# design.net
KiCad netlist of a schematic drawn in Altium Designer
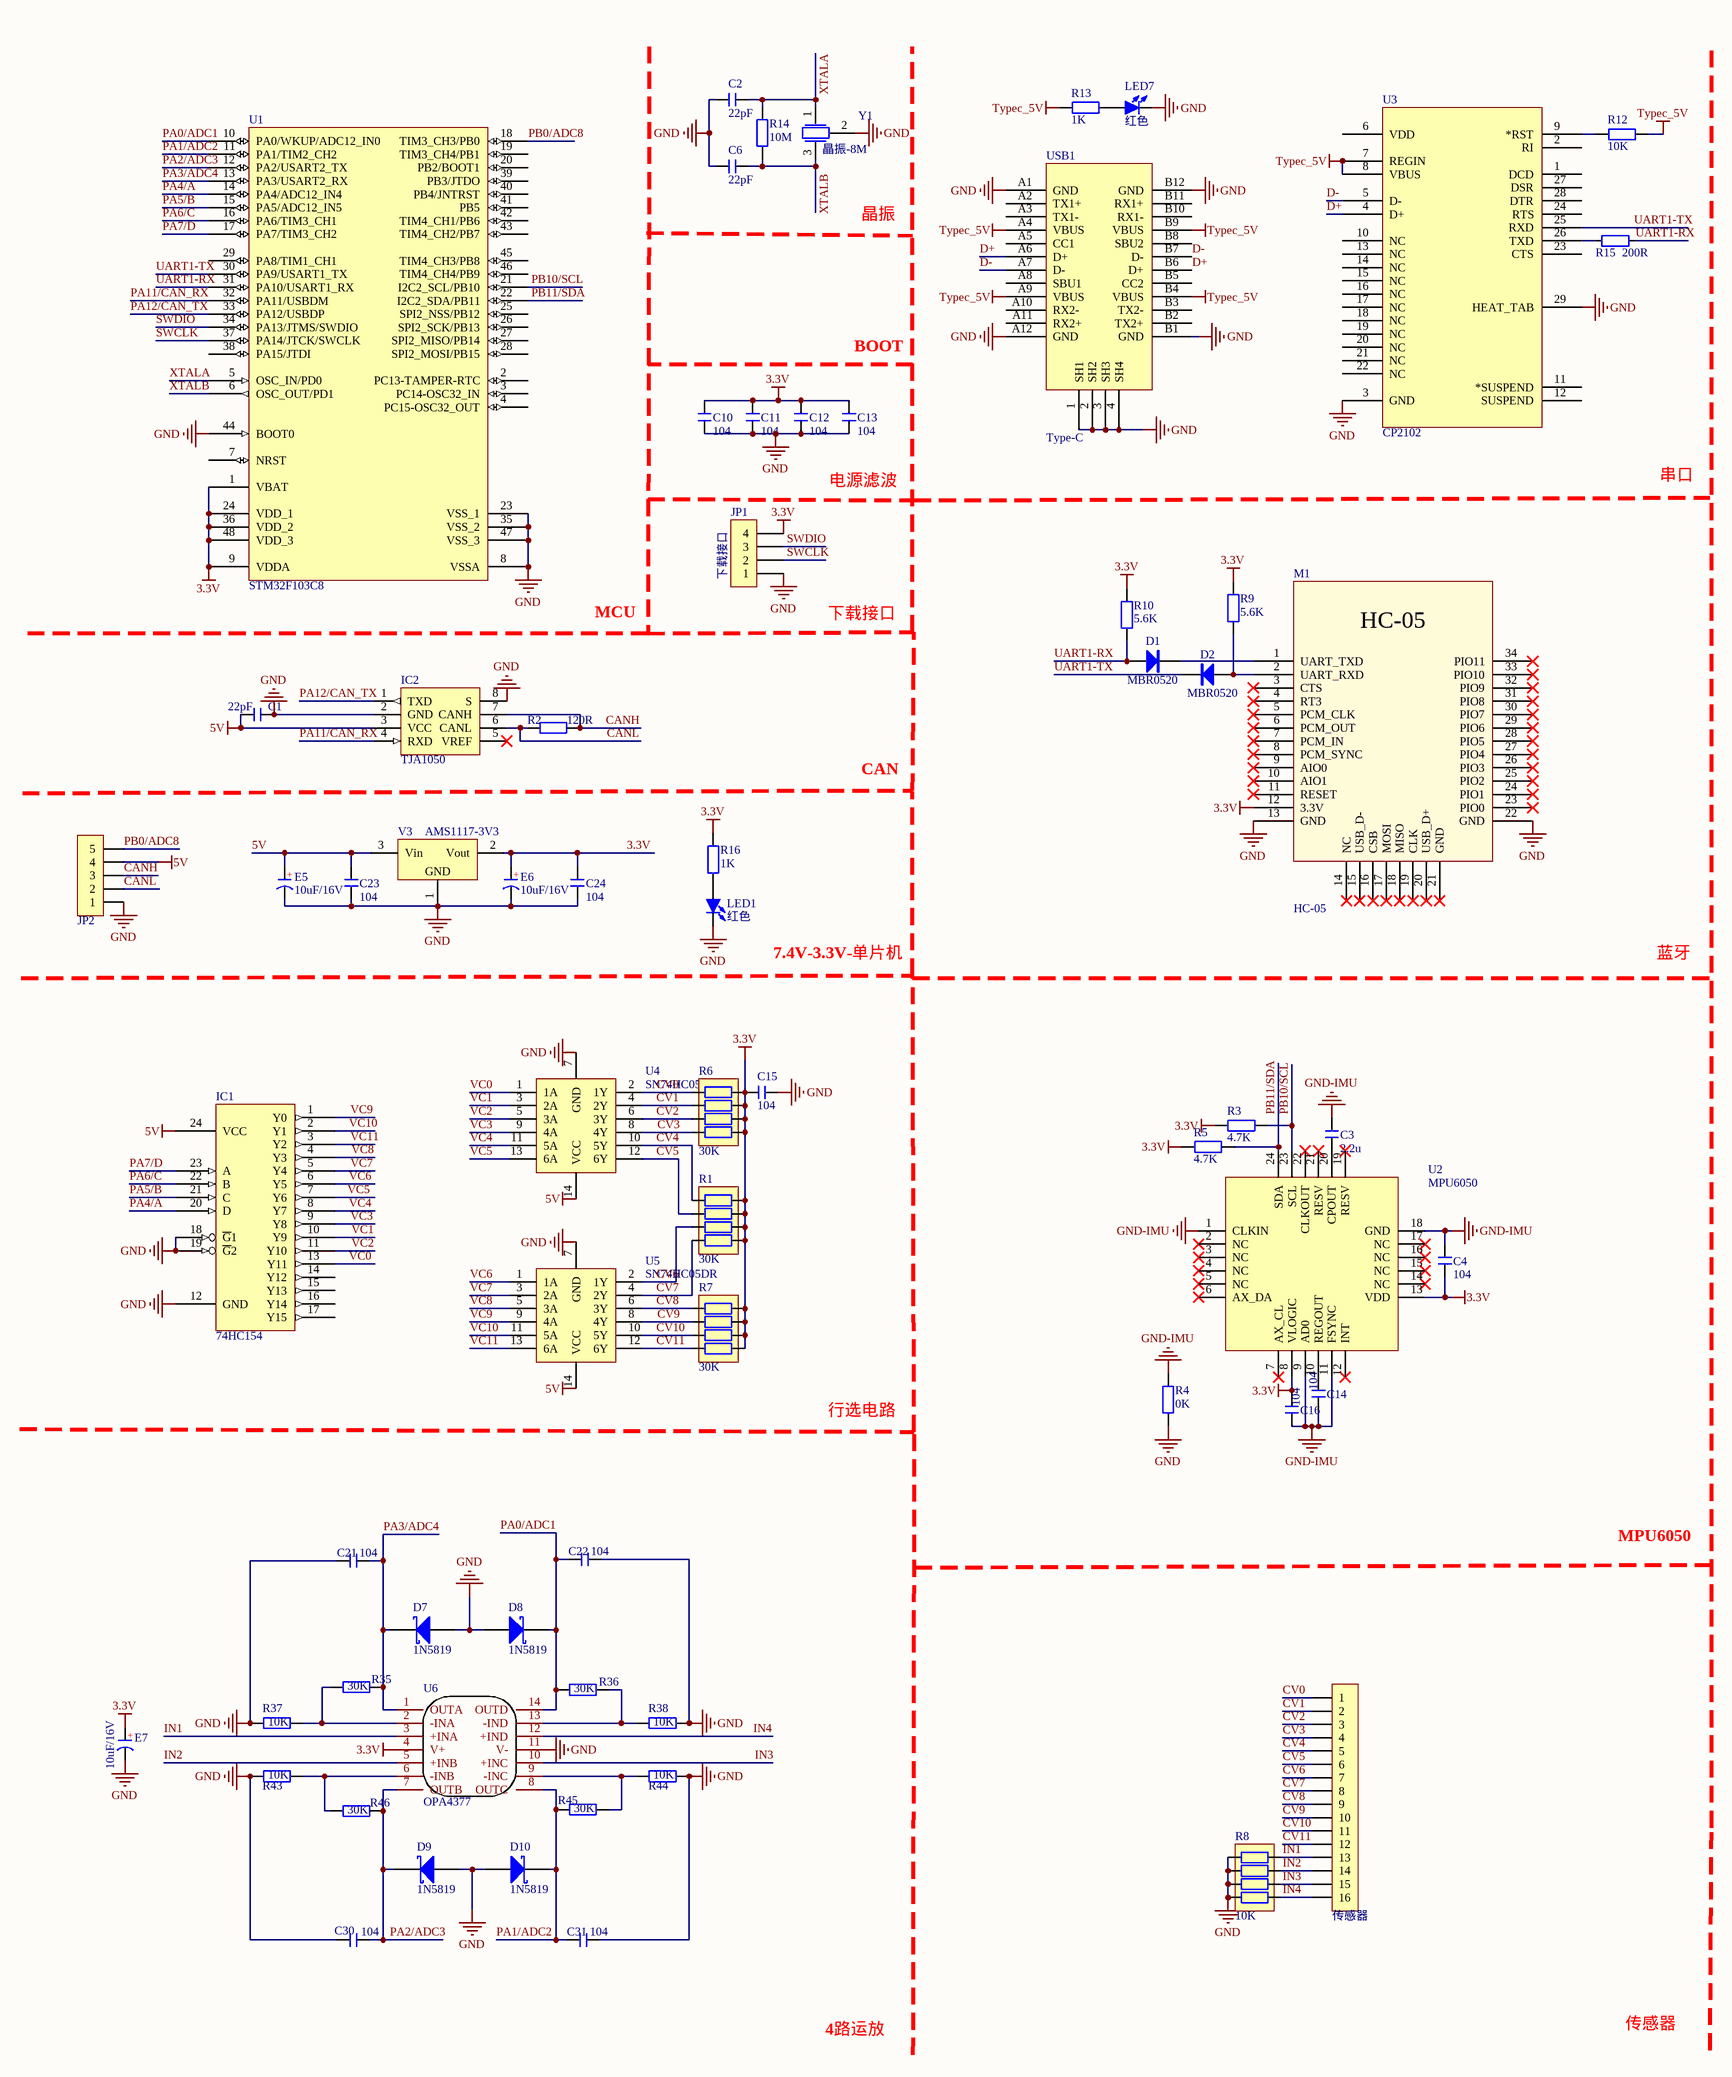
[diagram p0: 足底压力.SchDoc]

(export (version "E")
  (design (tool "Eeschema 10.0.6"))
  (components
    (comp (ref "C1")
      (value "22pF")
      (footprint "C 0402_L")
      (description "贴片电容")
      (libsource (lib "0.1 - 电阻-电容-电感") (part "C"))
    )
    (comp (ref "C2")
      (value "22pF")
      (footprint "C 0402_L")
      (description "贴片电容")
      (libsource (lib "0.1 - 电阻-电容-电感") (part "C"))
    )
    (comp (ref "C3")
      (value "2.2u")
      (footprint "C 0402_L")
      (description "贴片电容")
      (libsource (lib "0.1 - 电阻-电容-电感") (part "C"))
    )
    (comp (ref "C4")
      (value "104")
      (footprint "C 0402_L")
      (description "贴片电容")
      (libsource (lib "0.1 - 电阻-电容-电感") (part "C"))
    )
    (comp (ref "C6")
      (value "22pF")
      (footprint "C 0402_L")
      (description "贴片电容")
      (libsource (lib "0.1 - 电阻-电容-电感") (part "C"))
    )
    (comp (ref "C10")
      (value "104")
      (footprint "C 0402_L")
      (description "贴片电容")
      (libsource (lib "0.1 - 电阻-电容-电感") (part "C"))
    )
    (comp (ref "C11")
      (value "104")
      (footprint "C 0402_L")
      (description "贴片电容")
      (libsource (lib "0.1 - 电阻-电容-电感") (part "C"))
    )
    (comp (ref "C12")
      (value "104")
      (footprint "C 0402_L")
      (description "贴片电容")
      (libsource (lib "0.1 - 电阻-电容-电感") (part "C"))
    )
    (comp (ref "C13")
      (value "104")
      (footprint "C 0402_L")
      (description "贴片电容")
      (libsource (lib "0.1 - 电阻-电容-电感") (part "C"))
    )
    (comp (ref "C14")
      (value "104")
      (footprint "C 0402_L")
      (description "贴片电容")
      (libsource (lib "0.1 - 电阻-电容-电感") (part "C"))
    )
    (comp (ref "C15")
      (value "104")
      (footprint "C 0402_L")
      (description "贴片电容")
      (libsource (lib "0.1 - 电阻-电容-电感") (part "C"))
    )
    (comp (ref "C16")
      (value "104")
      (footprint "C 0402_L")
      (description "贴片电容")
      (libsource (lib "0.1 - 电阻-电容-电感") (part "C"))
    )
    (comp (ref "C21")
      (value "104")
      (footprint "C 0402_L")
      (description "贴片电容")
      (libsource (lib "0.1 - 电阻-电容-电感") (part "C"))
    )
    (comp (ref "C22")
      (value "104")
      (footprint "C 0402_L")
      (description "贴片电容")
      (libsource (lib "0.1 - 电阻-电容-电感") (part "C"))
    )
    (comp (ref "C23")
      (value "104")
      (footprint "C 0402_L")
      (description "贴片电容")
      (libsource (lib "0.1 - 电阻-电容-电感") (part "C"))
    )
    (comp (ref "C24")
      (value "104")
      (footprint "C 0402_L")
      (description "贴片电容")
      (libsource (lib "0.1 - 电阻-电容-电感") (part "C"))
    )
    (comp (ref "C30")
      (value "104")
      (footprint "C 0402_L")
      (description "贴片电容")
      (libsource (lib "0.1 - 电阻-电容-电感") (part "C"))
    )
    (comp (ref "C31")
      (value "104")
      (footprint "C 0402_L")
      (description "贴片电容")
      (libsource (lib "0.1 - 电阻-电容-电感") (part "C"))
    )
    (comp (ref "D1")
      (value "MBR0520")
      (footprint "SOD-123")
      (description "整流二极管")
      (libsource (lib "0.2 -  二极管-整流桥") (part "1N4007"))
    )
    (comp (ref "D2")
      (value "MBR0520")
      (footprint "SOD-123")
      (description "整流二极管")
      (libsource (lib "0.2 -  二极管-整流桥") (part "1N4007"))
    )
    (comp (ref "D7")
      (value "1N5819")
      (footprint "SOD-123")
      (description "肖特基二极管")
      (libsource (lib "0.2 -  二极管-整流桥") (part "1N5819"))
    )
    (comp (ref "D8")
      (value "1N5819")
      (footprint "SOD-123")
      (description "肖特基二极管")
      (libsource (lib "0.2 -  二极管-整流桥") (part "1N5819"))
    )
    (comp (ref "D9")
      (value "1N5819")
      (footprint "SOD-123")
      (description "肖特基二极管")
      (libsource (lib "0.2 -  二极管-整流桥") (part "1N5819"))
    )
    (comp (ref "D10")
      (value "1N5819")
      (footprint "SOD-123")
      (description "肖特基二极管")
      (libsource (lib "0.2 -  二极管-整流桥") (part "1N5819"))
    )
    (comp (ref "E5")
      (value "10uF/16V")
      (footprint "CD A(3216)")
      (description "贴片钽电容")
      (libsource (lib "0.1 - 电阻-电容-电感") (part "CT"))
    )
    (comp (ref "E6")
      (value "10uF/16V")
      (footprint "CD A(3216)")
      (description "贴片钽电容")
      (libsource (lib "0.1 - 电阻-电容-电感") (part "CT"))
    )
    (comp (ref "E7")
      (value "10uF/16V")
      (footprint "CD A(3216)")
      (description "贴片钽电容")
      (libsource (lib "0.1 - 电阻-电容-电感") (part "CT"))
    )
    (comp (ref "IC1")
      (value "74HC154")
      (footprint "SOP24_N")
      (description "4线转16线译码器")
      (libsource (lib "74系列芯片") (part "74HC154"))
    )
    (comp (ref "IC2")
      (value "TJA1050")
      (footprint "SOP8_L")
      (description "CAN总线收发芯片")
      (libsource (lib "1.0 - 常见芯片") (part "TJA1050"))
    )
    (comp (ref "JP1")
      (value "下载接口")
      (footprint "下载接口")
      (description "Jlink下载接口")
      (libsource (lib "金手指") (part "下载接口"))
    )
    (comp (ref "JP2")
      (value "HDR-1X5")
      (footprint "HDR2.54-M-LI-5P")
      (description "5P接插件")
      (libsource (lib "5.3 - 接插件-脚距2.54 (100mil) ") (part "Header 5"))
    )
    (comp (ref "LED1")
      (value "红色")
      (footprint "LED 0603R")
      (description "贴片LED")
      (libsource (lib "0.3 - LED发光二极管") (part "LED-SMD"))
    )
    (comp (ref "LED7")
      (value "红色")
      (footprint "LED 0603R")
      (description "贴片LED")
      (libsource (lib "0.3 - LED发光二极管") (part "LED-SMD"))
    )
    (comp (ref "M1")
      (value "HC-05")
      (footprint "HC-05")
      (description "串口蓝牙模块")
      (libsource (lib "模块") (part "HC-05"))
    )
    (comp (ref "R1")
      (value "30K")
      (footprint "RCA-8P4R-0603")
      (description "贴片排阻")
      (libsource (lib "0.1 - 电阻-电容-电感") (part "R-8P4R"))
    )
    (comp (ref "R2")
      (value "120R")
      (footprint "R 0402_L")
      (description "贴片电阻")
      (libsource (lib "0.1 - 电阻-电容-电感") (part "R"))
    )
    (comp (ref "R3")
      (value "4.7K")
      (footprint "R 0402_L")
      (description "贴片电阻")
      (libsource (lib "0.1 - 电阻-电容-电感") (part "R"))
    )
    (comp (ref "R4")
      (value "0K")
      (footprint "R 0402_L")
      (description "贴片电阻")
      (libsource (lib "0.1 - 电阻-电容-电感") (part "R"))
    )
    (comp (ref "R5")
      (value "4.7K")
      (footprint "R 0402_L")
      (description "贴片电阻")
      (libsource (lib "0.1 - 电阻-电容-电感") (part "R"))
    )
    (comp (ref "R6")
      (value "30K")
      (footprint "RCA-8P4R-0603")
      (description "贴片排阻")
      (libsource (lib "0.1 - 电阻-电容-电感") (part "R-8P4R"))
    )
    (comp (ref "R7")
      (value "30K")
      (footprint "RCA-8P4R-0603")
      (description "贴片排阻")
      (libsource (lib "0.1 - 电阻-电容-电感") (part "R-8P4R"))
    )
    (comp (ref "R8")
      (value "10K")
      (footprint "RCA-8P4R-0603")
      (description "贴片排阻")
      (libsource (lib "") (part "R-8P4R_1"))
    )
    (comp (ref "R9")
      (value "5.6K")
      (footprint "R 0402_L")
      (description "贴片电阻")
      (libsource (lib "0.1 - 电阻-电容-电感") (part "R"))
    )
    (comp (ref "R10")
      (value "5.6K")
      (footprint "R 0402_L")
      (description "贴片电阻")
      (libsource (lib "0.1 - 电阻-电容-电感") (part "R"))
    )
    (comp (ref "R12")
      (value "10K")
      (footprint "R 0402_L")
      (description "贴片电阻")
      (libsource (lib "0.1 - 电阻-电容-电感") (part "R"))
    )
    (comp (ref "R13")
      (value "1K")
      (footprint "R 0402_L")
      (description "贴片电阻")
      (libsource (lib "0.1 - 电阻-电容-电感") (part "R"))
    )
    (comp (ref "R14")
      (value "10M")
      (footprint "R 0402_L")
      (description "贴片电阻")
      (libsource (lib "0.1 - 电阻-电容-电感") (part "R"))
    )
    (comp (ref "R15")
      (value "200R")
      (footprint "RES_0402")
      (description "Resistor")
      (libsource (lib "MyPcbLib") (part "电阻-0402"))
    )
    (comp (ref "R16")
      (value "1K")
      (footprint "R 0402_L")
      (description "贴片电阻")
      (libsource (lib "0.1 - 电阻-电容-电感") (part "R"))
    )
    (comp (ref "R35")
      (value "30K")
      (footprint "R 0402_L")
      (description "贴片电阻")
      (libsource (lib "0.1 - 电阻-电容-电感") (part "R"))
    )
    (comp (ref "R36")
      (value "30K")
      (footprint "R 0402_L")
      (description "贴片电阻")
      (libsource (lib "0.1 - 电阻-电容-电感") (part "R"))
    )
    (comp (ref "R37")
      (value "10K")
      (footprint "R 0402_L")
      (description "贴片电阻")
      (libsource (lib "0.1 - 电阻-电容-电感") (part "R"))
    )
    (comp (ref "R38")
      (value "10K")
      (footprint "R 0402_L")
      (description "贴片电阻")
      (libsource (lib "0.1 - 电阻-电容-电感") (part "R"))
    )
    (comp (ref "R43")
      (value "10K")
      (footprint "R 0402_L")
      (description "贴片电阻")
      (libsource (lib "0.1 - 电阻-电容-电感") (part "R"))
    )
    (comp (ref "R44")
      (value "10K")
      (footprint "R 0402_L")
      (description "贴片电阻")
      (libsource (lib "0.1 - 电阻-电容-电感") (part "R"))
    )
    (comp (ref "R45")
      (value "30K")
      (footprint "R 0402_L")
      (description "贴片电阻")
      (libsource (lib "0.1 - 电阻-电容-电感") (part "R"))
    )
    (comp (ref "R46")
      (value "30K")
      (footprint "R 0402_L")
      (description "贴片电阻")
      (libsource (lib "0.1 - 电阻-电容-电感") (part "R"))
    )
    (comp (ref "U1")
      (value "STM32F103C8")
      (footprint "LQFP48 7X7_L")
      (description "Flaah:64/RAM:20/IO:36")
      (libsource (lib "STM32系列单片机") (part "STM32F103C8"))
    )
    (comp (ref "U2")
      (value "MPU6050")
      (footprint "QFN24 4x4_L")
      (description "数字运动传感器")
      (libsource (lib "传感元件") (part "MPU6050"))
    )
    (comp (ref "U3")
      (value "CP2102")
      (footprint "QFN-28")
      (description "USB转TTL")
      (libsource (lib "mLib") (part "CP2102"))
    )
    (comp (ref "U4")
      (value "SN74HC05DR")
      (footprint "SOP14")
      (libsource (lib "1.4 - 74系列TTL芯片") (part "SN74HC05DR"))
    )
    (comp (ref "U5")
      (value "SN74HC05DR")
      (footprint "SOP14")
      (libsource (lib "1.4 - 74系列TTL芯片") (part "SN74HC05DR"))
    )
    (comp (ref "U6")
      (value "OPA4377")
      (footprint "TSSOP14_L")
      (description "4路运放")
      (libsource (lib "运放-功放") (part "OPA4377"))
    )
    (comp (ref "USB1")
      (value "Type-C")
      (footprint "USB-C-SMD_16P")
      (libsource (lib "0.8 - 以太网-音频-USB插座") (part "USB-Type-C-TOP"))
    )
    (comp (ref "V3")
      (value "AMS1117-3V3")
      (footprint "SOT223_L")
      (description "三端稳压芯片")
      (libsource (lib "1.1 - 电源类芯片") (part "AMS1117"))
    )
    (comp (ref "Y1")
      (value "晶振-8M")
      (footprint "XTAL3*7")
      (libsource (lib "2.0 - 保险丝-晶振-光耦") (part "XTAL-3P"))
    )
    (comp (ref "传感器")
      (value "HDR-1X16")
      (footprint "XH2.54-WI-16P")
      (description "16P接插件")
      (libsource (lib "5.3 - 接插件-脚距2.54 (100mil) ") (part "Header 16"))
    )
  )
  (nets
    (net (code "1") (name "/CANH") (class "Default")
      (node (ref "IC2") (pin "7") (pinfunction "CANH_7") (pintype "passive"))
      (node (ref "JP2") (pin "3") (pinfunction "3_3") (pintype "passive"))
      (node (ref "R2") (pin "1") (pinfunction "1_1") (pintype "passive"))
    )
    (net (code "2") (name "/CANL") (class "Default")
      (node (ref "IC2") (pin "6") (pinfunction "CANL_6") (pintype "passive"))
      (node (ref "JP2") (pin "2") (pinfunction "2_2") (pintype "passive"))
      (node (ref "R2") (pin "2") (pinfunction "2_2") (pintype "passive"))
    )
    (net (code "3") (name "/CV0") (class "Default")
      (node (ref "R6") (pin "1") (pinfunction "1_1") (pintype "passive"))
      (node (ref "U4") (pin "2") (pinfunction "1Y_2") (pintype "passive"))
      (node (ref "传感器") (pin "1") (pinfunction "1_1") (pintype "passive"))
    )
    (net (code "4") (name "/CV1") (class "Default")
      (node (ref "R6") (pin "2") (pinfunction "2_2") (pintype "passive"))
      (node (ref "U4") (pin "4") (pinfunction "2Y_4") (pintype "passive"))
      (node (ref "传感器") (pin "2") (pinfunction "2_2") (pintype "passive"))
    )
    (net (code "5") (name "/CV2") (class "Default")
      (node (ref "R6") (pin "3") (pinfunction "3_3") (pintype "passive"))
      (node (ref "U4") (pin "6") (pinfunction "3Y_6") (pintype "passive"))
      (node (ref "传感器") (pin "3") (pinfunction "3_3") (pintype "passive"))
    )
    (net (code "6") (name "/CV3") (class "Default")
      (node (ref "R6") (pin "4") (pinfunction "4_4") (pintype "passive"))
      (node (ref "U4") (pin "8") (pinfunction "4Y_8") (pintype "passive"))
      (node (ref "传感器") (pin "4") (pinfunction "4_4") (pintype "passive"))
    )
    (net (code "7") (name "/CV4") (class "Default")
      (node (ref "R1") (pin "1") (pinfunction "1_1") (pintype "passive"))
      (node (ref "U4") (pin "10") (pinfunction "5Y_10") (pintype "passive"))
      (node (ref "传感器") (pin "5") (pinfunction "5_5") (pintype "passive"))
    )
    (net (code "8") (name "/CV5") (class "Default")
      (node (ref "R1") (pin "2") (pinfunction "2_2") (pintype "passive"))
      (node (ref "U4") (pin "12") (pinfunction "6Y_12") (pintype "passive"))
      (node (ref "传感器") (pin "6") (pinfunction "6_6") (pintype "passive"))
    )
    (net (code "9") (name "/CV6") (class "Default")
      (node (ref "R1") (pin "3") (pinfunction "3_3") (pintype "passive"))
      (node (ref "U5") (pin "2") (pinfunction "1Y_2") (pintype "passive"))
      (node (ref "传感器") (pin "7") (pinfunction "7_7") (pintype "passive"))
    )
    (net (code "10") (name "/CV7") (class "Default")
      (node (ref "R1") (pin "4") (pinfunction "4_4") (pintype "passive"))
      (node (ref "U5") (pin "4") (pinfunction "2Y_4") (pintype "passive"))
      (node (ref "传感器") (pin "8") (pinfunction "8_8") (pintype "passive"))
    )
    (net (code "11") (name "/CV8") (class "Default")
      (node (ref "R7") (pin "1") (pinfunction "1_1") (pintype "passive"))
      (node (ref "U5") (pin "6") (pinfunction "3Y_6") (pintype "passive"))
      (node (ref "传感器") (pin "9") (pinfunction "9_9") (pintype "passive"))
    )
    (net (code "12") (name "/CV9") (class "Default")
      (node (ref "R7") (pin "2") (pinfunction "2_2") (pintype "passive"))
      (node (ref "U5") (pin "8") (pinfunction "4Y_8") (pintype "passive"))
      (node (ref "传感器") (pin "10") (pinfunction "10_10") (pintype "passive"))
    )
    (net (code "13") (name "/CV10") (class "Default")
      (node (ref "R7") (pin "3") (pinfunction "3_3") (pintype "passive"))
      (node (ref "U5") (pin "10") (pinfunction "5Y_10") (pintype "passive"))
      (node (ref "传感器") (pin "11") (pinfunction "11_11") (pintype "passive"))
    )
    (net (code "14") (name "/CV11") (class "Default")
      (node (ref "R7") (pin "4") (pinfunction "4_4") (pintype "passive"))
      (node (ref "U5") (pin "12") (pinfunction "6Y_12") (pintype "passive"))
      (node (ref "传感器") (pin "12") (pinfunction "12_12") (pintype "passive"))
    )
    (net (code "15") (name "/D+") (class "Default")
      (node (ref "U3") (pin "4") (pinfunction "D+_4") (pintype "passive"))
      (node (ref "USB1") (pin "A6") (pinfunction "D+_A6") (pintype "passive"))
      (node (ref "USB1") (pin "B6") (pinfunction "D+_B6") (pintype "passive"))
    )
    (net (code "16") (name "/D-") (class "Default")
      (node (ref "U3") (pin "5") (pinfunction "D-_5") (pintype "passive"))
      (node (ref "USB1") (pin "A7") (pinfunction "D-_A7") (pintype "passive"))
      (node (ref "USB1") (pin "B7") (pinfunction "D-_B7") (pintype "passive"))
    )
    (net (code "17") (name "/IN1") (class "Default")
      (node (ref "R8") (pin "5") (pinfunction "5_5") (pintype "passive"))
      (node (ref "U6") (pin "3") (pinfunction "+INA_3") (pintype "passive"))
      (node (ref "传感器") (pin "13") (pinfunction "13_13") (pintype "passive"))
    )
    (net (code "18") (name "/IN2") (class "Default")
      (node (ref "R8") (pin "6") (pinfunction "6_6") (pintype "passive"))
      (node (ref "U6") (pin "5") (pinfunction "+INB_5") (pintype "passive"))
      (node (ref "传感器") (pin "14") (pinfunction "14_14") (pintype "passive"))
    )
    (net (code "19") (name "/IN3") (class "Default")
      (node (ref "R8") (pin "7") (pinfunction "7_7") (pintype "passive"))
      (node (ref "U6") (pin "10") (pinfunction "+INC_10") (pintype "passive"))
      (node (ref "传感器") (pin "15") (pinfunction "15_15") (pintype "passive"))
    )
    (net (code "20") (name "/IN4") (class "Default")
      (node (ref "R8") (pin "8") (pinfunction "8_8") (pintype "passive"))
      (node (ref "U6") (pin "12") (pinfunction "+IND_12") (pintype "passive"))
      (node (ref "传感器") (pin "16") (pinfunction "16_16") (pintype "passive"))
    )
    (net (code "21") (name "/PA0{slash}ADC1") (class "Default")
      (node (ref "C22") (pin "1") (pinfunction "1_1") (pintype "passive"))
      (node (ref "D8") (pin "2") (pinfunction "K_2") (pintype "passive"))
      (node (ref "R36") (pin "1") (pinfunction "1_1") (pintype "passive"))
      (node (ref "U1") (pin "10") (pinfunction "PA0/WKUP/ADC12_IN0_10") (pintype "bidirectional"))
      (node (ref "U6") (pin "14") (pinfunction "OUTD_14") (pintype "passive"))
    )
    (net (code "22") (name "/PA1{slash}ADC2") (class "Default")
      (node (ref "C31") (pin "1") (pinfunction "1_1") (pintype "passive"))
      (node (ref "D10") (pin "2") (pinfunction "K_2") (pintype "passive"))
      (node (ref "R45") (pin "1") (pinfunction "1_1") (pintype "passive"))
      (node (ref "U1") (pin "11") (pinfunction "PA1/TIM2_CH2_11") (pintype "bidirectional"))
      (node (ref "U6") (pin "8") (pinfunction "OUTC_8") (pintype "passive"))
    )
    (net (code "23") (name "/PA2{slash}ADC3") (class "Default")
      (node (ref "C30") (pin "1") (pinfunction "1_1") (pintype "passive"))
      (node (ref "D9") (pin "2") (pinfunction "K_2") (pintype "passive"))
      (node (ref "R46") (pin "2") (pinfunction "2_2") (pintype "passive"))
      (node (ref "U1") (pin "12") (pinfunction "PA2/USART2_TX_12") (pintype "bidirectional"))
      (node (ref "U6") (pin "7") (pinfunction "OUTB_7") (pintype "passive"))
    )
    (net (code "24") (name "/PA3{slash}ADC4") (class "Default")
      (node (ref "C21") (pin "2") (pinfunction "2_2") (pintype "passive"))
      (node (ref "D7") (pin "2") (pinfunction "K_2") (pintype "passive"))
      (node (ref "R35") (pin "2") (pinfunction "2_2") (pintype "passive"))
      (node (ref "U1") (pin "13") (pinfunction "PA3/USART2_RX_13") (pintype "bidirectional"))
      (node (ref "U6") (pin "1") (pinfunction "OUTA_1") (pintype "passive"))
    )
    (net (code "25") (name "/PA4{slash}A") (class "Default")
      (node (ref "IC1") (pin "20") (pinfunction "D_20") (pintype "input"))
      (node (ref "U1") (pin "14") (pinfunction "PA4/ADC12_IN4_14") (pintype "bidirectional"))
    )
    (net (code "26") (name "/PA5{slash}B") (class "Default")
      (node (ref "IC1") (pin "21") (pinfunction "C_21") (pintype "input"))
      (node (ref "U1") (pin "15") (pinfunction "PA5/ADC12_IN5_15") (pintype "bidirectional"))
    )
    (net (code "27") (name "/PA6{slash}C") (class "Default")
      (node (ref "IC1") (pin "22") (pinfunction "B_22") (pintype "input"))
      (node (ref "U1") (pin "16") (pinfunction "PA6/TIM3_CH1_16") (pintype "bidirectional"))
    )
    (net (code "28") (name "/PA7{slash}D") (class "Default")
      (node (ref "IC1") (pin "23") (pinfunction "A_23") (pintype "input"))
      (node (ref "U1") (pin "17") (pinfunction "PA7/TIM3_CH2_17") (pintype "bidirectional"))
    )
    (net (code "29") (name "/PA11{slash}CAN_RX") (class "Default")
      (node (ref "IC2") (pin "4") (pinfunction "RXD_4") (pintype "input"))
      (node (ref "U1") (pin "32") (pinfunction "PA11/USBDM_32") (pintype "bidirectional"))
    )
    (net (code "30") (name "/PA12{slash}CAN_TX") (class "Default")
      (node (ref "IC2") (pin "1") (pinfunction "TXD_1") (pintype "output"))
      (node (ref "U1") (pin "33") (pinfunction "PA12/USBDP_33") (pintype "bidirectional"))
    )
    (net (code "31") (name "/PB0{slash}ADC8") (class "Default")
      (node (ref "JP2") (pin "5") (pinfunction "5_5") (pintype "passive"))
      (node (ref "U1") (pin "18") (pinfunction "TIM3_CH3/PB0_18") (pintype "bidirectional"))
    )
    (net (code "32") (name "/PB10{slash}SCL") (class "Default")
      (node (ref "R3") (pin "2") (pinfunction "2_2") (pintype "passive"))
      (node (ref "U1") (pin "21") (pinfunction "I2C2_SCL/PB10_21") (pintype "bidirectional"))
      (node (ref "U2") (pin "23") (pinfunction "SCL_23") (pintype "passive"))
    )
    (net (code "33") (name "/PB11{slash}SDA") (class "Default")
      (node (ref "R5") (pin "2") (pinfunction "2_2") (pintype "passive"))
      (node (ref "U1") (pin "22") (pinfunction "I2C2_SDA/PB11_22") (pintype "bidirectional"))
      (node (ref "U2") (pin "24") (pinfunction "SDA_24") (pintype "passive"))
    )
    (net (code "34") (name "/SWCLK") (class "Default")
      (node (ref "JP1") (pin "2") (pinfunction "2_2") (pintype "passive"))
      (node (ref "U1") (pin "37") (pinfunction "PA14/JTCK/SWCLK_37") (pintype "bidirectional"))
    )
    (net (code "35") (name "/SWDIO") (class "Default")
      (node (ref "JP1") (pin "3") (pinfunction "3_3") (pintype "passive"))
      (node (ref "U1") (pin "34") (pinfunction "PA13/JTMS/SWDIO_34") (pintype "bidirectional"))
    )
    (net (code "36") (name "/UART1-RX") (class "Default")
      (node (ref "D1") (pin "1") (pinfunction "A_1") (pintype "passive"))
      (node (ref "R10") (pin "1") (pinfunction "1_1") (pintype "passive"))
      (node (ref "R15") (pin "1") (pinfunction "1_1") (pintype "passive"))
      (node (ref "U1") (pin "31") (pinfunction "PA10/USART1_RX_31") (pintype "bidirectional"))
    )
    (net (code "37") (name "/UART1-TX") (class "Default")
      (node (ref "D2") (pin "2") (pinfunction "K_2") (pintype "passive"))
      (node (ref "U1") (pin "30") (pinfunction "PA9/USART1_TX_30") (pintype "bidirectional"))
      (node (ref "U3") (pin "25") (pinfunction "RXD_25") (pintype "passive"))
    )
    (net (code "38") (name "/VC0") (class "Default")
      (node (ref "IC1") (pin "13") (pinfunction "Y11_13") (pintype "output"))
      (node (ref "U4") (pin "1") (pinfunction "1A_1") (pintype "passive"))
    )
    (net (code "39") (name "/VC1") (class "Default")
      (node (ref "IC1") (pin "10") (pinfunction "Y9_10") (pintype "output"))
      (node (ref "U4") (pin "3") (pinfunction "2A_3") (pintype "passive"))
    )
    (net (code "40") (name "/VC2") (class "Default")
      (node (ref "IC1") (pin "11") (pinfunction "Y10_11") (pintype "output"))
      (node (ref "U4") (pin "5") (pinfunction "3A_5") (pintype "passive"))
    )
    (net (code "41") (name "/VC3") (class "Default")
      (node (ref "IC1") (pin "9") (pinfunction "Y8_9") (pintype "output"))
      (node (ref "U4") (pin "9") (pinfunction "4A_9") (pintype "passive"))
    )
    (net (code "42") (name "/VC4") (class "Default")
      (node (ref "IC1") (pin "8") (pinfunction "Y7_8") (pintype "output"))
      (node (ref "U4") (pin "11") (pinfunction "5A_11") (pintype "passive"))
    )
    (net (code "43") (name "/VC5") (class "Default")
      (node (ref "IC1") (pin "7") (pinfunction "Y6_7") (pintype "output"))
      (node (ref "U4") (pin "13") (pinfunction "6A_13") (pintype "passive"))
    )
    (net (code "44") (name "/VC6") (class "Default")
      (node (ref "IC1") (pin "6") (pinfunction "Y5_6") (pintype "output"))
      (node (ref "U5") (pin "1") (pinfunction "1A_1") (pintype "passive"))
    )
    (net (code "45") (name "/VC7") (class "Default")
      (node (ref "IC1") (pin "5") (pinfunction "Y4_5") (pintype "output"))
      (node (ref "U5") (pin "3") (pinfunction "2A_3") (pintype "passive"))
    )
    (net (code "46") (name "/VC8") (class "Default")
      (node (ref "IC1") (pin "4") (pinfunction "Y3_4") (pintype "output"))
      (node (ref "U5") (pin "5") (pinfunction "3A_5") (pintype "passive"))
    )
    (net (code "47") (name "/VC9") (class "Default")
      (node (ref "IC1") (pin "1") (pinfunction "Y0_1") (pintype "output"))
      (node (ref "U5") (pin "9") (pinfunction "4A_9") (pintype "passive"))
    )
    (net (code "48") (name "/VC10") (class "Default")
      (node (ref "IC1") (pin "2") (pinfunction "Y1_2") (pintype "output"))
      (node (ref "U5") (pin "11") (pinfunction "5A_11") (pintype "passive"))
    )
    (net (code "49") (name "/VC11") (class "Default")
      (node (ref "IC1") (pin "3") (pinfunction "Y2_3") (pintype "output"))
      (node (ref "U5") (pin "13") (pinfunction "6A_13") (pintype "passive"))
    )
    (net (code "50") (name "/XTALA") (class "Default")
      (node (ref "C2") (pin "2") (pinfunction "2_2") (pintype "passive"))
      (node (ref "R14") (pin "1") (pinfunction "1_1") (pintype "passive"))
      (node (ref "U1") (pin "5") (pinfunction "OSC_IN/PD0_5") (pintype "input"))
      (node (ref "Y1") (pin "1") (pinfunction "1_1") (pintype "passive"))
    )
    (net (code "51") (name "/XTALB") (class "Default")
      (node (ref "C6") (pin "2") (pinfunction "2_2") (pintype "passive"))
      (node (ref "R14") (pin "2") (pinfunction "2_2") (pintype "passive"))
      (node (ref "U1") (pin "6") (pinfunction "OSC_OUT/PD1_6") (pintype "output"))
      (node (ref "Y1") (pin "3") (pinfunction "3_3") (pintype "passive"))
    )
    (net (code "52") (name "3.3V") (class "Default")
      (node (ref "C10") (pin "2") (pinfunction "2_2") (pintype "passive"))
      (node (ref "C11") (pin "2") (pinfunction "2_2") (pintype "passive"))
      (node (ref "C12") (pin "2") (pinfunction "2_2") (pintype "passive"))
      (node (ref "C13") (pin "2") (pinfunction "2_2") (pintype "passive"))
      (node (ref "C15") (pin "1") (pinfunction "1_1") (pintype "passive"))
      (node (ref "C16") (pin "2") (pinfunction "2_2") (pintype "passive"))
      (node (ref "C24") (pin "2") (pinfunction "2_2") (pintype "passive"))
      (node (ref "C4") (pin "1") (pinfunction "1_1") (pintype "passive"))
      (node (ref "E6") (pin "1") (pinfunction "A_1") (pintype "passive"))
      (node (ref "E7") (pin "1") (pinfunction "A_1") (pintype "passive"))
      (node (ref "JP1") (pin "4") (pinfunction "4_4") (pintype "passive"))
      (node (ref "M1") (pin "12") (pinfunction "3.3V_12") (pintype "passive"))
      (node (ref "R1") (pin "5") (pinfunction "5_5") (pintype "passive"))
      (node (ref "R1") (pin "6") (pinfunction "6_6") (pintype "passive"))
      (node (ref "R1") (pin "7") (pinfunction "7_7") (pintype "passive"))
      (node (ref "R1") (pin "8") (pinfunction "8_8") (pintype "passive"))
      (node (ref "R10") (pin "2") (pinfunction "2_2") (pintype "passive"))
      (node (ref "R16") (pin "2") (pinfunction "2_2") (pintype "passive"))
      (node (ref "R3") (pin "1") (pinfunction "1_1") (pintype "passive"))
      (node (ref "R5") (pin "1") (pinfunction "1_1") (pintype "passive"))
      (node (ref "R6") (pin "5") (pinfunction "5_5") (pintype "passive"))
      (node (ref "R6") (pin "6") (pinfunction "6_6") (pintype "passive"))
      (node (ref "R6") (pin "7") (pinfunction "7_7") (pintype "passive"))
      (node (ref "R6") (pin "8") (pinfunction "8_8") (pintype "passive"))
      (node (ref "R7") (pin "5") (pinfunction "5_5") (pintype "passive"))
      (node (ref "R7") (pin "6") (pinfunction "6_6") (pintype "passive"))
      (node (ref "R7") (pin "7") (pinfunction "7_7") (pintype "passive"))
      (node (ref "R7") (pin "8") (pinfunction "8_8") (pintype "passive"))
      (node (ref "R9") (pin "2") (pinfunction "2_2") (pintype "passive"))
      (node (ref "U1") (pin "1") (pinfunction "VBAT_1") (pintype "power_in"))
      (node (ref "U1") (pin "24") (pinfunction "VDD_1_24") (pintype "power_in"))
      (node (ref "U1") (pin "36") (pinfunction "VDD_2_36") (pintype "power_in"))
      (node (ref "U1") (pin "48") (pinfunction "VDD_3_48") (pintype "power_in"))
      (node (ref "U1") (pin "9") (pinfunction "VDDA_9") (pintype "power_in"))
      (node (ref "U2") (pin "13") (pinfunction "VDD_13") (pintype "passive"))
      (node (ref "U2") (pin "8") (pinfunction "VLOGIC_8") (pintype "passive"))
      (node (ref "U6") (pin "4") (pinfunction "V+_4") (pintype "passive"))
      (node (ref "V3") (pin "2") (pinfunction "Vout_2") (pintype "passive"))
    )
    (net (code "53") (name "5V") (class "Default")
      (node (ref "C1") (pin "2") (pinfunction "2_2") (pintype "passive"))
      (node (ref "C23") (pin "2") (pinfunction "2_2") (pintype "passive"))
      (node (ref "E5") (pin "1") (pinfunction "A_1") (pintype "passive"))
      (node (ref "IC1") (pin "24") (pinfunction "VCC_24") (pintype "power_in"))
      (node (ref "IC2") (pin "3") (pinfunction "VCC_3") (pintype "passive"))
      (node (ref "JP2") (pin "4") (pinfunction "4_4") (pintype "passive"))
      (node (ref "U4") (pin "14") (pinfunction "VCC_14") (pintype "passive"))
      (node (ref "U5") (pin "14") (pinfunction "VCC_14") (pintype "passive"))
      (node (ref "V3") (pin "3") (pinfunction "Vin_3") (pintype "passive"))
    )
    (net (code "54") (name "GND") (class "Default")
      (node (ref "C1") (pin "1") (pinfunction "1_1") (pintype "passive"))
      (node (ref "C10") (pin "1") (pinfunction "1_1") (pintype "passive"))
      (node (ref "C11") (pin "1") (pinfunction "1_1") (pintype "passive"))
      (node (ref "C12") (pin "1") (pinfunction "1_1") (pintype "passive"))
      (node (ref "C13") (pin "1") (pinfunction "1_1") (pintype "passive"))
      (node (ref "C15") (pin "2") (pinfunction "2_2") (pintype "passive"))
      (node (ref "C2") (pin "1") (pinfunction "1_1") (pintype "passive"))
      (node (ref "C21") (pin "1") (pinfunction "1_1") (pintype "passive"))
      (node (ref "C22") (pin "2") (pinfunction "2_2") (pintype "passive"))
      (node (ref "C23") (pin "1") (pinfunction "1_1") (pintype "passive"))
      (node (ref "C24") (pin "1") (pinfunction "1_1") (pintype "passive"))
      (node (ref "C30") (pin "2") (pinfunction "2_2") (pintype "passive"))
      (node (ref "C31") (pin "2") (pinfunction "2_2") (pintype "passive"))
      (node (ref "C6") (pin "1") (pinfunction "1_1") (pintype "passive"))
      (node (ref "D10") (pin "1") (pinfunction "A_1") (pintype "passive"))
      (node (ref "D7") (pin "1") (pinfunction "A_1") (pintype "passive"))
      (node (ref "D8") (pin "1") (pinfunction "A_1") (pintype "passive"))
      (node (ref "D9") (pin "1") (pinfunction "A_1") (pintype "passive"))
      (node (ref "E5") (pin "2") (pinfunction "K_2") (pintype "passive"))
      (node (ref "E6") (pin "2") (pinfunction "K_2") (pintype "passive"))
      (node (ref "E7") (pin "2") (pinfunction "K_2") (pintype "passive"))
      (node (ref "IC1") (pin "12") (pinfunction "GND_12") (pintype "power_in"))
      (node (ref "IC1") (pin "18") (pinfunction "~{G}1_18") (pintype "input"))
      (node (ref "IC1") (pin "19") (pinfunction "~{G}2_19") (pintype "input"))
      (node (ref "IC2") (pin "2") (pinfunction "GND_2") (pintype "passive"))
      (node (ref "IC2") (pin "8") (pinfunction "S_8") (pintype "passive"))
      (node (ref "JP1") (pin "1") (pinfunction "1_1") (pintype "passive"))
      (node (ref "JP2") (pin "1") (pinfunction "1_1") (pintype "passive"))
      (node (ref "LED1") (pin "2") (pinfunction "K_2") (pintype "passive"))
      (node (ref "LED7") (pin "2") (pinfunction "K_2") (pintype "passive"))
      (node (ref "M1") (pin "13") (pinfunction "GND_13") (pintype "passive"))
      (node (ref "M1") (pin "22") (pinfunction "GND_22") (pintype "passive"))
      (node (ref "R37") (pin "2") (pinfunction "2_2") (pintype "passive"))
      (node (ref "R38") (pin "1") (pinfunction "1_1") (pintype "passive"))
      (node (ref "R4") (pin "1") (pinfunction "1_1") (pintype "passive"))
      (node (ref "R43") (pin "1") (pinfunction "1_1") (pintype "passive"))
      (node (ref "R44") (pin "2") (pinfunction "2_2") (pintype "passive"))
      (node (ref "R8") (pin "1") (pinfunction "1_1") (pintype "passive"))
      (node (ref "R8") (pin "2") (pinfunction "2_2") (pintype "passive"))
      (node (ref "R8") (pin "3") (pinfunction "3_3") (pintype "passive"))
      (node (ref "R8") (pin "4") (pinfunction "4_4") (pintype "passive"))
      (node (ref "U1") (pin "23") (pinfunction "VSS_1_23") (pintype "power_in"))
      (node (ref "U1") (pin "35") (pinfunction "VSS_2_35") (pintype "power_in"))
      (node (ref "U1") (pin "44") (pinfunction "BOOT0_44") (pintype "input"))
      (node (ref "U1") (pin "47") (pinfunction "VSS_3_47") (pintype "power_in"))
      (node (ref "U1") (pin "8") (pinfunction "VSSA_8") (pintype "power_in"))
      (node (ref "U3") (pin "29") (pinfunction "HEAT_TAB_29") (pintype "passive"))
      (node (ref "U3") (pin "3") (pinfunction "GND_3") (pintype "passive"))
      (node (ref "U4") (pin "7") (pinfunction "GND_7") (pintype "passive"))
      (node (ref "U5") (pin "7") (pinfunction "GND_7") (pintype "passive"))
      (node (ref "U6") (pin "11") (pinfunction "V-_11") (pintype "passive"))
      (node (ref "USB1") (pin "1") (pinfunction "SH1_1") (pintype "passive"))
      (node (ref "USB1") (pin "2") (pinfunction "SH2_2") (pintype "passive"))
      (node (ref "USB1") (pin "3") (pinfunction "SH3_3") (pintype "passive"))
      (node (ref "USB1") (pin "4") (pinfunction "SH4_4") (pintype "passive"))
      (node (ref "USB1") (pin "A1") (pinfunction "GND_A1") (pintype "passive"))
      (node (ref "USB1") (pin "A12") (pinfunction "GND_A12") (pintype "passive"))
      (node (ref "USB1") (pin "B1") (pinfunction "GND_B1") (pintype "passive"))
      (node (ref "USB1") (pin "B12") (pinfunction "GND_B12") (pintype "passive"))
      (node (ref "V3") (pin "1") (pinfunction "GND_1") (pintype "passive"))
      (node (ref "Y1") (pin "2") (pinfunction "2_2") (pintype "passive"))
    )
    (net (code "55") (name "GND-IMU") (class "Default")
      (node (ref "C14") (pin "1") (pinfunction "1_1") (pintype "passive"))
      (node (ref "C16") (pin "1") (pinfunction "1_1") (pintype "passive"))
      (node (ref "C3") (pin "1") (pinfunction "1_1") (pintype "passive"))
      (node (ref "C4") (pin "2") (pinfunction "2_2") (pintype "passive"))
      (node (ref "R4") (pin "2") (pinfunction "2_2") (pintype "passive"))
      (node (ref "U2") (pin "1") (pinfunction "CLKIN_1") (pintype "passive"))
      (node (ref "U2") (pin "11") (pinfunction "FSYNC_11") (pintype "passive"))
      (node (ref "U2") (pin "18") (pinfunction "GND_18") (pintype "passive"))
      (node (ref "U2") (pin "9") (pinfunction "AD0_9") (pintype "passive"))
    )
    (net (code "56") (name "Net-(D1-K)") (class "Default")
      (node (ref "D1") (pin "2") (pinfunction "K_2") (pintype "passive"))
      (node (ref "M1") (pin "1") (pinfunction "UART_TXD_1") (pintype "passive"))
    )
    (net (code "57") (name "Net-(D2-A)") (class "Default")
      (node (ref "D2") (pin "1") (pinfunction "A_1") (pintype "passive"))
      (node (ref "M1") (pin "2") (pinfunction "UART_RXD_2") (pintype "passive"))
      (node (ref "R9") (pin "1") (pinfunction "1_1") (pintype "passive"))
    )
    (net (code "58") (name "Net-(LED1-A)") (class "Default")
      (node (ref "LED1") (pin "1") (pinfunction "A_1") (pintype "passive"))
      (node (ref "R16") (pin "1") (pinfunction "1_1") (pintype "passive"))
    )
    (net (code "59") (name "Net-(LED7-A)") (class "Default")
      (node (ref "LED7") (pin "1") (pinfunction "A_1") (pintype "passive"))
      (node (ref "R13") (pin "1") (pinfunction "1_1") (pintype "passive"))
    )
    (net (code "60") (name "Net-(U2-CPOUT)") (class "Default")
      (node (ref "C3") (pin "2") (pinfunction "2_2") (pintype "passive"))
      (node (ref "U2") (pin "20") (pinfunction "CPOUT_20") (pintype "passive"))
    )
    (net (code "61") (name "Net-(U2-REGOUT)") (class "Default")
      (node (ref "C14") (pin "2") (pinfunction "2_2") (pintype "passive"))
      (node (ref "U2") (pin "10") (pinfunction "REGOUT_10") (pintype "passive"))
    )
    (net (code "62") (name "Net-(U3-*RST)") (class "Default")
      (node (ref "R12") (pin "2") (pinfunction "2_2") (pintype "passive"))
      (node (ref "U3") (pin "9") (pinfunction "*RST_9") (pintype "passive"))
    )
    (net (code "63") (name "Net-(U3-TXD)") (class "Default")
      (node (ref "R15") (pin "2") (pinfunction "2_2") (pintype "passive"))
      (node (ref "U3") (pin "26") (pinfunction "TXD_26") (pintype "passive"))
    )
    (net (code "64") (name "Net-(U6--INA)") (class "Default")
      (node (ref "R35") (pin "1") (pinfunction "1_1") (pintype "passive"))
      (node (ref "R37") (pin "1") (pinfunction "1_1") (pintype "passive"))
      (node (ref "U6") (pin "2") (pinfunction "-INA_2") (pintype "passive"))
    )
    (net (code "65") (name "Net-(U6--INB)") (class "Default")
      (node (ref "R43") (pin "2") (pinfunction "2_2") (pintype "passive"))
      (node (ref "R46") (pin "1") (pinfunction "1_1") (pintype "passive"))
      (node (ref "U6") (pin "6") (pinfunction "-INB_6") (pintype "passive"))
    )
    (net (code "66") (name "Net-(U6--INC)") (class "Default")
      (node (ref "R44") (pin "1") (pinfunction "1_1") (pintype "passive"))
      (node (ref "R45") (pin "2") (pinfunction "2_2") (pintype "passive"))
      (node (ref "U6") (pin "9") (pinfunction "-INC_9") (pintype "passive"))
    )
    (net (code "67") (name "Net-(U6--IND)") (class "Default")
      (node (ref "R36") (pin "2") (pinfunction "2_2") (pintype "passive"))
      (node (ref "R38") (pin "2") (pinfunction "2_2") (pintype "passive"))
      (node (ref "U6") (pin "13") (pinfunction "-IND_13") (pintype "passive"))
    )
    (net (code "68") (name "Typec_5V") (class "Default")
      (node (ref "R12") (pin "1") (pinfunction "1_1") (pintype "passive"))
      (node (ref "R13") (pin "2") (pinfunction "2_2") (pintype "passive"))
      (node (ref "U3") (pin "7") (pinfunction "REGIN_7") (pintype "passive"))
      (node (ref "U3") (pin "8") (pinfunction "VBUS_8") (pintype "passive"))
      (node (ref "USB1") (pin "A4") (pinfunction "VBUS_A4") (pintype "passive"))
      (node (ref "USB1") (pin "A9") (pinfunction "VBUS_A9") (pintype "passive"))
      (node (ref "USB1") (pin "B4") (pinfunction "VBUS_B4") (pintype "passive"))
      (node (ref "USB1") (pin "B9") (pinfunction "VBUS_B9") (pintype "passive"))
    )
    (net (code "69") (name "unconnected-(IC1-Y12-Pad14)") (class "Default")
      (node (ref "IC1") (pin "14") (pinfunction "Y12_14") (pintype "output"))
    )
    (net (code "70") (name "unconnected-(IC1-Y13-Pad15)") (class "Default")
      (node (ref "IC1") (pin "15") (pinfunction "Y13_15") (pintype "output"))
    )
    (net (code "71") (name "unconnected-(IC1-Y14-Pad16)") (class "Default")
      (node (ref "IC1") (pin "16") (pinfunction "Y14_16") (pintype "output"))
    )
    (net (code "72") (name "unconnected-(IC1-Y15-Pad17)") (class "Default")
      (node (ref "IC1") (pin "17") (pinfunction "Y15_17") (pintype "output"))
    )
    (net (code "73") (name "unconnected-(IC2-VREF-Pad5)") (class "Default")
      (node (ref "IC2") (pin "5") (pinfunction "VREF_5") (pintype "passive+no_connect"))
    )
    (net (code "74") (name "unconnected-(M1-AIO0-Pad9)") (class "Default")
      (node (ref "M1") (pin "9") (pinfunction "AIO0_9") (pintype "passive+no_connect"))
    )
    (net (code "75") (name "unconnected-(M1-AIO1-Pad10)") (class "Default")
      (node (ref "M1") (pin "10") (pinfunction "AIO1_10") (pintype "passive+no_connect"))
    )
    (net (code "76") (name "unconnected-(M1-CLK-Pad19)") (class "Default")
      (node (ref "M1") (pin "19") (pinfunction "CLK_19") (pintype "passive+no_connect"))
    )
    (net (code "77") (name "unconnected-(M1-CSB-Pad16)") (class "Default")
      (node (ref "M1") (pin "16") (pinfunction "CSB_16") (pintype "passive+no_connect"))
    )
    (net (code "78") (name "unconnected-(M1-CTS-Pad3)") (class "Default")
      (node (ref "M1") (pin "3") (pinfunction "CTS_3") (pintype "passive+no_connect"))
    )
    (net (code "79") (name "unconnected-(M1-GND-Pad21)") (class "Default")
      (node (ref "M1") (pin "21") (pinfunction "GND_21") (pintype "passive+no_connect"))
    )
    (net (code "80") (name "unconnected-(M1-MISO-Pad18)") (class "Default")
      (node (ref "M1") (pin "18") (pinfunction "MISO_18") (pintype "passive+no_connect"))
    )
    (net (code "81") (name "unconnected-(M1-MOSI-Pad17)") (class "Default")
      (node (ref "M1") (pin "17") (pinfunction "MOSI_17") (pintype "passive+no_connect"))
    )
    (net (code "82") (name "unconnected-(M1-NC-Pad14)") (class "Default")
      (node (ref "M1") (pin "14") (pinfunction "NC_14") (pintype "passive+no_connect"))
    )
    (net (code "83") (name "unconnected-(M1-PCM_CLK-Pad5)") (class "Default")
      (node (ref "M1") (pin "5") (pinfunction "PCM_CLK_5") (pintype "passive+no_connect"))
    )
    (net (code "84") (name "unconnected-(M1-PCM_IN-Pad7)") (class "Default")
      (node (ref "M1") (pin "7") (pinfunction "PCM_IN_7") (pintype "passive+no_connect"))
    )
    (net (code "85") (name "unconnected-(M1-PCM_OUT-Pad6)") (class "Default")
      (node (ref "M1") (pin "6") (pinfunction "PCM_OUT_6") (pintype "passive+no_connect"))
    )
    (net (code "86") (name "unconnected-(M1-PCM_SYNC-Pad8)") (class "Default")
      (node (ref "M1") (pin "8") (pinfunction "PCM_SYNC_8") (pintype "passive+no_connect"))
    )
    (net (code "87") (name "unconnected-(M1-PIO0-Pad23)") (class "Default")
      (node (ref "M1") (pin "23") (pinfunction "PIO0_23") (pintype "passive+no_connect"))
    )
    (net (code "88") (name "unconnected-(M1-PIO1-Pad24)") (class "Default")
      (node (ref "M1") (pin "24") (pinfunction "PIO1_24") (pintype "passive+no_connect"))
    )
    (net (code "89") (name "unconnected-(M1-PIO2-Pad25)") (class "Default")
      (node (ref "M1") (pin "25") (pinfunction "PIO2_25") (pintype "passive+no_connect"))
    )
    (net (code "90") (name "unconnected-(M1-PIO3-Pad26)") (class "Default")
      (node (ref "M1") (pin "26") (pinfunction "PIO3_26") (pintype "passive+no_connect"))
    )
    (net (code "91") (name "unconnected-(M1-PIO4-Pad27)") (class "Default")
      (node (ref "M1") (pin "27") (pinfunction "PIO4_27") (pintype "passive+no_connect"))
    )
    (net (code "92") (name "unconnected-(M1-PIO5-Pad28)") (class "Default")
      (node (ref "M1") (pin "28") (pinfunction "PIO5_28") (pintype "passive+no_connect"))
    )
    (net (code "93") (name "unconnected-(M1-PIO6-Pad29)") (class "Default")
      (node (ref "M1") (pin "29") (pinfunction "PIO6_29") (pintype "passive+no_connect"))
    )
    (net (code "94") (name "unconnected-(M1-PIO7-Pad30)") (class "Default")
      (node (ref "M1") (pin "30") (pinfunction "PIO7_30") (pintype "passive+no_connect"))
    )
    (net (code "95") (name "unconnected-(M1-PIO8-Pad31)") (class "Default")
      (node (ref "M1") (pin "31") (pinfunction "PIO8_31") (pintype "passive+no_connect"))
    )
    (net (code "96") (name "unconnected-(M1-PIO9-Pad32)") (class "Default")
      (node (ref "M1") (pin "32") (pinfunction "PIO9_32") (pintype "passive+no_connect"))
    )
    (net (code "97") (name "unconnected-(M1-PIO10-Pad33)") (class "Default")
      (node (ref "M1") (pin "33") (pinfunction "PIO10_33") (pintype "passive+no_connect"))
    )
    (net (code "98") (name "unconnected-(M1-PIO11-Pad34)") (class "Default")
      (node (ref "M1") (pin "34") (pinfunction "PIO11_34") (pintype "passive+no_connect"))
    )
    (net (code "99") (name "unconnected-(M1-RESET-Pad11)") (class "Default")
      (node (ref "M1") (pin "11") (pinfunction "RESET_11") (pintype "passive+no_connect"))
    )
    (net (code "100") (name "unconnected-(M1-RT3-Pad4)") (class "Default")
      (node (ref "M1") (pin "4") (pinfunction "RT3_4") (pintype "passive+no_connect"))
    )
    (net (code "101") (name "unconnected-(M1-USB_D+-Pad20)") (class "Default")
      (node (ref "M1") (pin "20") (pinfunction "USB_D+_20") (pintype "passive+no_connect"))
    )
    (net (code "102") (name "unconnected-(M1-USB_D--Pad15)") (class "Default")
      (node (ref "M1") (pin "15") (pinfunction "USB_D-_15") (pintype "passive+no_connect"))
    )
    (net (code "103") (name "unconnected-(U1-NRST-Pad7)") (class "Default")
      (node (ref "U1") (pin "7") (pinfunction "NRST_7") (pintype "bidirectional"))
    )
    (net (code "104") (name "unconnected-(U1-PA8{slash}TIM1_CH1-Pad29)") (class "Default")
      (node (ref "U1") (pin "29") (pinfunction "PA8/TIM1_CH1_29") (pintype "bidirectional"))
    )
    (net (code "105") (name "unconnected-(U1-PA15{slash}JTDI-Pad38)") (class "Default")
      (node (ref "U1") (pin "38") (pinfunction "PA15/JTDI_38") (pintype "bidirectional"))
    )
    (net (code "106") (name "unconnected-(U1-PB2{slash}BOOT1-Pad20)") (class "Default")
      (node (ref "U1") (pin "20") (pinfunction "PB2/BOOT1_20") (pintype "bidirectional"))
    )
    (net (code "107") (name "unconnected-(U1-PB3{slash}JTDO-Pad39)") (class "Default")
      (node (ref "U1") (pin "39") (pinfunction "PB3/JTDO_39") (pintype "bidirectional"))
    )
    (net (code "108") (name "unconnected-(U1-PB4{slash}JNTRST-Pad40)") (class "Default")
      (node (ref "U1") (pin "40") (pinfunction "PB4/JNTRST_40") (pintype "bidirectional"))
    )
    (net (code "109") (name "unconnected-(U1-PB5-Pad41)") (class "Default")
      (node (ref "U1") (pin "41") (pinfunction "PB5_41") (pintype "bidirectional"))
    )
    (net (code "110") (name "unconnected-(U1-PC13-TAMPER-RTC-Pad2)") (class "Default")
      (node (ref "U1") (pin "2") (pinfunction "PC13-TAMPER-RTC_2") (pintype "bidirectional"))
    )
    (net (code "111") (name "unconnected-(U1-PC14-OSC32_IN-Pad3)") (class "Default")
      (node (ref "U1") (pin "3") (pinfunction "PC14-OSC32_IN_3") (pintype "bidirectional"))
    )
    (net (code "112") (name "unconnected-(U1-PC15-OSC32_OUT-Pad4)") (class "Default")
      (node (ref "U1") (pin "4") (pinfunction "PC15-OSC32_OUT_4") (pintype "bidirectional"))
    )
    (net (code "113") (name "unconnected-(U1-SPI2_MISO{slash}PB14-Pad27)") (class "Default")
      (node (ref "U1") (pin "27") (pinfunction "SPI2_MISO/PB14_27") (pintype "bidirectional"))
    )
    (net (code "114") (name "unconnected-(U1-SPI2_MOSI{slash}PB15-Pad28)") (class "Default")
      (node (ref "U1") (pin "28") (pinfunction "SPI2_MOSI/PB15_28") (pintype "bidirectional"))
    )
    (net (code "115") (name "unconnected-(U1-SPI2_NSS{slash}PB12-Pad25)") (class "Default")
      (node (ref "U1") (pin "25") (pinfunction "SPI2_NSS/PB12_25") (pintype "bidirectional"))
    )
    (net (code "116") (name "unconnected-(U1-SPI2_SCK{slash}PB13-Pad26)") (class "Default")
      (node (ref "U1") (pin "26") (pinfunction "SPI2_SCK/PB13_26") (pintype "bidirectional"))
    )
    (net (code "117") (name "unconnected-(U1-TIM3_CH4{slash}PB1-Pad19)") (class "Default")
      (node (ref "U1") (pin "19") (pinfunction "TIM3_CH4/PB1_19") (pintype "bidirectional"))
    )
    (net (code "118") (name "unconnected-(U1-TIM4_CH1{slash}PB6-Pad42)") (class "Default")
      (node (ref "U1") (pin "42") (pinfunction "TIM4_CH1/PB6_42") (pintype "bidirectional"))
    )
    (net (code "119") (name "unconnected-(U1-TIM4_CH2{slash}PB7-Pad43)") (class "Default")
      (node (ref "U1") (pin "43") (pinfunction "TIM4_CH2/PB7_43") (pintype "bidirectional"))
    )
    (net (code "120") (name "unconnected-(U1-TIM4_CH3{slash}PB8-Pad45)") (class "Default")
      (node (ref "U1") (pin "45") (pinfunction "TIM4_CH3/PB8_45") (pintype "bidirectional"))
    )
    (net (code "121") (name "unconnected-(U1-TIM4_CH4{slash}PB9-Pad46)") (class "Default")
      (node (ref "U1") (pin "46") (pinfunction "TIM4_CH4/PB9_46") (pintype "bidirectional"))
    )
    (net (code "122") (name "unconnected-(U2-AX_CL-Pad7)") (class "Default")
      (node (ref "U2") (pin "7") (pinfunction "AX_CL_7") (pintype "passive+no_connect"))
    )
    (net (code "123") (name "unconnected-(U2-AX_DA-Pad6)") (class "Default")
      (node (ref "U2") (pin "6") (pinfunction "AX_DA_6") (pintype "passive+no_connect"))
    )
    (net (code "124") (name "unconnected-(U2-CLKOUT-Pad22)") (class "Default")
      (node (ref "U2") (pin "22") (pinfunction "CLKOUT_22") (pintype "passive+no_connect"))
    )
    (net (code "125") (name "unconnected-(U2-INT-Pad12)") (class "Default")
      (node (ref "U2") (pin "12") (pinfunction "INT_12") (pintype "passive+no_connect"))
    )
    (net (code "126") (name "unconnected-(U2-NC-Pad2)") (class "Default")
      (node (ref "U2") (pin "2") (pinfunction "NC_2") (pintype "passive+no_connect"))
    )
    (net (code "127") (name "unconnected-(U2-NC-Pad3)") (class "Default")
      (node (ref "U2") (pin "3") (pinfunction "NC_3") (pintype "passive+no_connect"))
    )
    (net (code "128") (name "unconnected-(U2-NC-Pad4)") (class "Default")
      (node (ref "U2") (pin "4") (pinfunction "NC_4") (pintype "passive+no_connect"))
    )
    (net (code "129") (name "unconnected-(U2-NC-Pad5)") (class "Default")
      (node (ref "U2") (pin "5") (pinfunction "NC_5") (pintype "passive+no_connect"))
    )
    (net (code "130") (name "unconnected-(U2-NC-Pad14)") (class "Default")
      (node (ref "U2") (pin "14") (pinfunction "NC_14") (pintype "passive+no_connect"))
    )
    (net (code "131") (name "unconnected-(U2-NC-Pad15)") (class "Default")
      (node (ref "U2") (pin "15") (pinfunction "NC_15") (pintype "passive+no_connect"))
    )
    (net (code "132") (name "unconnected-(U2-NC-Pad16)") (class "Default")
      (node (ref "U2") (pin "16") (pinfunction "NC_16") (pintype "passive+no_connect"))
    )
    (net (code "133") (name "unconnected-(U2-NC-Pad17)") (class "Default")
      (node (ref "U2") (pin "17") (pinfunction "NC_17") (pintype "passive+no_connect"))
    )
    (net (code "134") (name "unconnected-(U2-RESV-Pad19)") (class "Default")
      (node (ref "U2") (pin "19") (pinfunction "RESV_19") (pintype "passive+no_connect"))
    )
    (net (code "135") (name "unconnected-(U2-RESV-Pad21)") (class "Default")
      (node (ref "U2") (pin "21") (pinfunction "RESV_21") (pintype "passive+no_connect"))
    )
    (net (code "136") (name "unconnected-(U3-*SUSPEND-Pad11)") (class "Default")
      (node (ref "U3") (pin "11") (pinfunction "*SUSPEND_11") (pintype "passive"))
    )
    (net (code "137") (name "unconnected-(U3-CTS-Pad23)") (class "Default")
      (node (ref "U3") (pin "23") (pinfunction "CTS_23") (pintype "passive"))
    )
    (net (code "138") (name "unconnected-(U3-DCD-Pad1)") (class "Default")
      (node (ref "U3") (pin "1") (pinfunction "DCD_1") (pintype "passive"))
    )
    (net (code "139") (name "unconnected-(U3-DSR-Pad27)") (class "Default")
      (node (ref "U3") (pin "27") (pinfunction "DSR_27") (pintype "passive"))
    )
    (net (code "140") (name "unconnected-(U3-DTR-Pad28)") (class "Default")
      (node (ref "U3") (pin "28") (pinfunction "DTR_28") (pintype "passive"))
    )
    (net (code "141") (name "unconnected-(U3-NC-Pad10)") (class "Default")
      (node (ref "U3") (pin "10") (pinfunction "NC_10") (pintype "passive"))
    )
    (net (code "142") (name "unconnected-(U3-NC-Pad13)") (class "Default")
      (node (ref "U3") (pin "13") (pinfunction "NC_13") (pintype "passive"))
    )
    (net (code "143") (name "unconnected-(U3-NC-Pad14)") (class "Default")
      (node (ref "U3") (pin "14") (pinfunction "NC_14") (pintype "passive"))
    )
    (net (code "144") (name "unconnected-(U3-NC-Pad15)") (class "Default")
      (node (ref "U3") (pin "15") (pinfunction "NC_15") (pintype "passive"))
    )
    (net (code "145") (name "unconnected-(U3-NC-Pad16)") (class "Default")
      (node (ref "U3") (pin "16") (pinfunction "NC_16") (pintype "passive"))
    )
    (net (code "146") (name "unconnected-(U3-NC-Pad17)") (class "Default")
      (node (ref "U3") (pin "17") (pinfunction "NC_17") (pintype "passive"))
    )
    (net (code "147") (name "unconnected-(U3-NC-Pad18)") (class "Default")
      (node (ref "U3") (pin "18") (pinfunction "NC_18") (pintype "passive"))
    )
    (net (code "148") (name "unconnected-(U3-NC-Pad19)") (class "Default")
      (node (ref "U3") (pin "19") (pinfunction "NC_19") (pintype "passive"))
    )
    (net (code "149") (name "unconnected-(U3-NC-Pad20)") (class "Default")
      (node (ref "U3") (pin "20") (pinfunction "NC_20") (pintype "passive"))
    )
    (net (code "150") (name "unconnected-(U3-NC-Pad21)") (class "Default")
      (node (ref "U3") (pin "21") (pinfunction "NC_21") (pintype "passive"))
    )
    (net (code "151") (name "unconnected-(U3-NC-Pad22)") (class "Default")
      (node (ref "U3") (pin "22") (pinfunction "NC_22") (pintype "passive"))
    )
    (net (code "152") (name "unconnected-(U3-RI-Pad2)") (class "Default")
      (node (ref "U3") (pin "2") (pinfunction "RI_2") (pintype "passive"))
    )
    (net (code "153") (name "unconnected-(U3-RTS-Pad24)") (class "Default")
      (node (ref "U3") (pin "24") (pinfunction "RTS_24") (pintype "passive"))
    )
    (net (code "154") (name "unconnected-(U3-SUSPEND-Pad12)") (class "Default")
      (node (ref "U3") (pin "12") (pinfunction "SUSPEND_12") (pintype "passive"))
    )
    (net (code "155") (name "unconnected-(U3-VDD-Pad6)") (class "Default")
      (node (ref "U3") (pin "6") (pinfunction "VDD_6") (pintype "passive"))
    )
    (net (code "156") (name "unconnected-(USB1-CC1-PadA5)") (class "Default")
      (node (ref "USB1") (pin "A5") (pinfunction "CC1_A5") (pintype "passive"))
    )
    (net (code "157") (name "unconnected-(USB1-CC2-PadB5)") (class "Default")
      (node (ref "USB1") (pin "B5") (pinfunction "CC2_B5") (pintype "passive"))
    )
    (net (code "158") (name "unconnected-(USB1-RX1+-PadB11)") (class "Default")
      (node (ref "USB1") (pin "B11") (pinfunction "RX1+_B11") (pintype "passive"))
    )
    (net (code "159") (name "unconnected-(USB1-RX1--PadB10)") (class "Default")
      (node (ref "USB1") (pin "B10") (pinfunction "RX1-_B10") (pintype "passive"))
    )
    (net (code "160") (name "unconnected-(USB1-RX2+-PadA11)") (class "Default")
      (node (ref "USB1") (pin "A11") (pinfunction "RX2+_A11") (pintype "passive"))
    )
    (net (code "161") (name "unconnected-(USB1-RX2--PadA10)") (class "Default")
      (node (ref "USB1") (pin "A10") (pinfunction "RX2-_A10") (pintype "passive"))
    )
    (net (code "162") (name "unconnected-(USB1-SBU1-PadA8)") (class "Default")
      (node (ref "USB1") (pin "A8") (pinfunction "SBU1_A8") (pintype "passive"))
    )
    (net (code "163") (name "unconnected-(USB1-SBU2-PadB8)") (class "Default")
      (node (ref "USB1") (pin "B8") (pinfunction "SBU2_B8") (pintype "passive"))
    )
    (net (code "164") (name "unconnected-(USB1-TX1+-PadA2)") (class "Default")
      (node (ref "USB1") (pin "A2") (pinfunction "TX1+_A2") (pintype "passive"))
    )
    (net (code "165") (name "unconnected-(USB1-TX1--PadA3)") (class "Default")
      (node (ref "USB1") (pin "A3") (pinfunction "TX1-_A3") (pintype "passive"))
    )
    (net (code "166") (name "unconnected-(USB1-TX2+-PadB2)") (class "Default")
      (node (ref "USB1") (pin "B2") (pinfunction "TX2+_B2") (pintype "passive"))
    )
    (net (code "167") (name "unconnected-(USB1-TX2--PadB3)") (class "Default")
      (node (ref "USB1") (pin "B3") (pinfunction "TX2-_B3") (pintype "passive"))
    )
  )
)
